# POWER_BANK_PART.net
KiCad netlist of a schematic drawn in Altium Designer
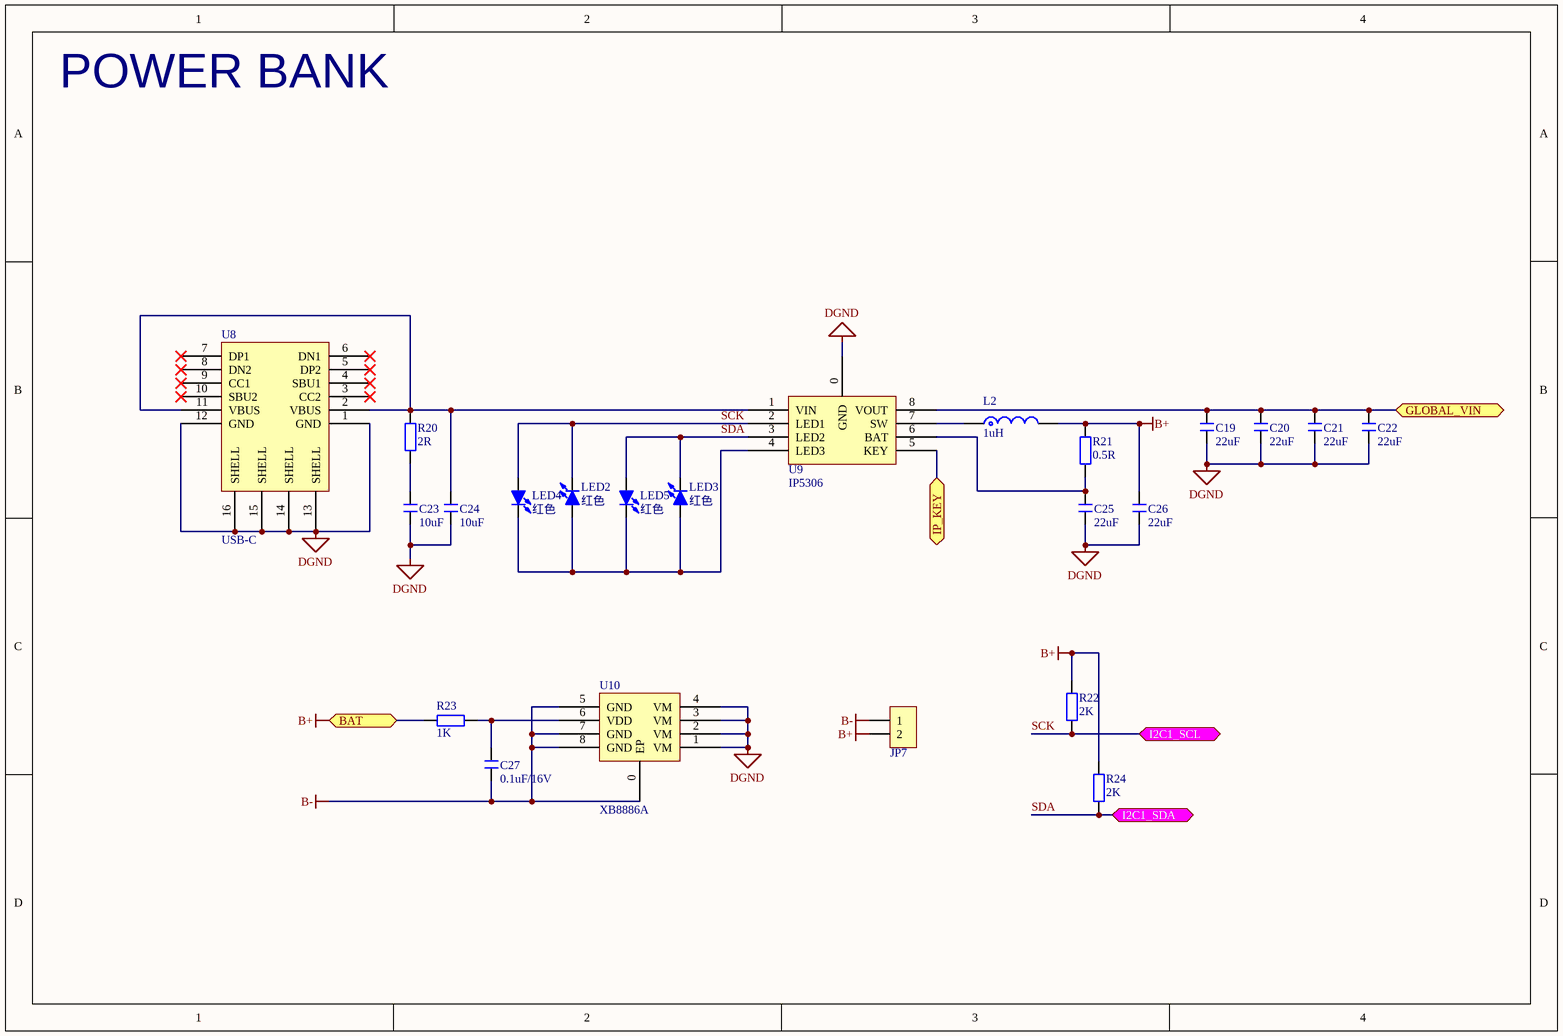
[diagram p0: POWER_BANK_PART.SchDoc]

(export (version "E")
  (design (tool "Eeschema 10.0.6"))
  (components
    (comp (ref "C19")
      (value "22uF")
      (footprint "C 0603_L")
      (description "无极性贴片电容")
      (fields (field (name "版权归属") "源创客"))
      (libsource (lib "3.1   - 电阻-电容-电感") (part "C"))
    )
    (comp (ref "C20")
      (value "22uF")
      (footprint "C 0603_L")
      (description "无极性贴片电容")
      (fields (field (name "版权归属") "源创客"))
      (libsource (lib "3.1   - 电阻-电容-电感") (part "C"))
    )
    (comp (ref "C21")
      (value "22uF")
      (footprint "C 0603_L")
      (description "无极性贴片电容")
      (fields (field (name "版权归属") "源创客"))
      (libsource (lib "3.1   - 电阻-电容-电感") (part "C"))
    )
    (comp (ref "C22")
      (value "22uF")
      (footprint "C 0603_L")
      (description "无极性贴片电容")
      (fields (field (name "版权归属") "源创客"))
      (libsource (lib "3.1   - 电阻-电容-电感") (part "C"))
    )
    (comp (ref "C23")
      (value "10uF")
      (footprint "C 0603_L")
      (description "无极性贴片电容")
      (fields (field (name "版权归属") "源创客"))
      (libsource (lib "3.1   - 电阻-电容-电感") (part "C"))
    )
    (comp (ref "C24")
      (value "10uF")
      (footprint "C 0603_L")
      (description "无极性贴片电容")
      (fields (field (name "版权归属") "源创客"))
      (libsource (lib "3.1   - 电阻-电容-电感") (part "C"))
    )
    (comp (ref "C25")
      (value "22uF")
      (footprint "C 0603_L")
      (description "无极性贴片电容")
      (fields (field (name "版权归属") "源创客"))
      (libsource (lib "3.1   - 电阻-电容-电感") (part "C"))
    )
    (comp (ref "C26")
      (value "22uF")
      (footprint "C 0603_L")
      (description "无极性贴片电容")
      (fields (field (name "版权归属") "源创客"))
      (libsource (lib "3.1   - 电阻-电容-电感") (part "C"))
    )
    (comp (ref "C27")
      (value "0.1uF/16V")
      (footprint "C 0603_L")
      (description "无极性贴片电容")
      (fields (field (name "版权归属") "源创客"))
      (libsource (lib "3.1   - 电阻-电容-电感") (part "C"))
    )
    (comp (ref "JP7")
      (value "HDR-1X2")
      (footprint "KF301-5.0-2P")
      (description "2P接插件")
      (fields (field (name "版权归属") "源创客"))
      (libsource (lib "4.9   - 接插件-脚距5.0") (part "Header 2"))
    )
    (comp (ref "L2")
      (value "1uH")
      (footprint "CD43")
      (description "贴片功率电感")
      (fields (field (name "版权归属") "源创客"))
      (libsource (lib "3.1   - 电阻-电容-电感") (part "L-CD"))
    )
    (comp (ref "LED2")
      (value "红色")
      (footprint "LED 0603W")
      (description "贴片LED")
      (fields (field (name "版权归属") "源创客"))
      (libsource (lib "9.1   - LED") (part "LED-SMD"))
    )
    (comp (ref "LED3")
      (value "红色")
      (footprint "LED 0603W")
      (description "贴片LED")
      (fields (field (name "版权归属") "源创客"))
      (libsource (lib "9.1   - LED") (part "LED-SMD"))
    )
    (comp (ref "LED4")
      (value "红色")
      (footprint "LED 0603W")
      (description "贴片LED")
      (fields (field (name "版权归属") "源创客"))
      (libsource (lib "9.1   - LED") (part "LED-SMD"))
    )
    (comp (ref "LED5")
      (value "红色")
      (footprint "LED 0603W")
      (description "贴片LED")
      (fields (field (name "版权归属") "源创客"))
      (libsource (lib "9.1   - LED") (part "LED-SMD"))
    )
    (comp (ref "R20")
      (value "2R")
      (footprint "R 0603_L")
      (description "贴片电阻")
      (fields (field (name "版权归属") "源创客"))
      (libsource (lib "3.1   - 电阻-电容-电感") (part "R"))
    )
    (comp (ref "R21")
      (value "0.5R")
      (footprint "R 0603_L")
      (description "贴片电阻")
      (fields (field (name "版权归属") "源创客"))
      (libsource (lib "3.1   - 电阻-电容-电感") (part "R"))
    )
    (comp (ref "R22")
      (value "2K")
      (footprint "R 0603_L")
      (description "贴片电阻")
      (fields (field (name "版权归属") "源创客"))
      (libsource (lib "3.1   - 电阻-电容-电感") (part "R"))
    )
    (comp (ref "R23")
      (value "1K")
      (footprint "R 0603_L")
      (description "贴片电阻")
      (fields (field (name "版权归属") "源创客"))
      (libsource (lib "3.1   - 电阻-电容-电感") (part "R"))
    )
    (comp (ref "R24")
      (value "2K")
      (footprint "R 0603_L")
      (description "贴片电阻")
      (fields (field (name "版权归属") "源创客"))
      (libsource (lib "3.1   - 电阻-电容-电感") (part "R"))
    )
    (comp (ref "U8")
      (value "USB-C")
      (footprint "USB-C-16")
      (description "USB-C型母接口")
      (fields (field (name "版权归属") "源创客"))
      (libsource (lib "示波器") (part "USB-C-16P"))
    )
    (comp (ref "U9")
      (value "IP5306")
      (footprint "SOP-8-G")
      (description "电源芯片")
      (libsource (lib "示波器") (part "IP5306"))
    )
    (comp (ref "U10")
      (value "XB8886A")
      (footprint "SOP-8-G")
      (description "锂电池保护芯片")
      (libsource (lib "示波器") (part "XB8886A"))
    )
  )
  (nets
    (net (code "1") (name "/GLOBAL_VIN") (class "Default")
      (node (ref "C19") (pin "1") (pinfunction "1_1") (pintype "passive"))
      (node (ref "C20") (pin "1") (pinfunction "1_1") (pintype "passive"))
      (node (ref "C21") (pin "1") (pinfunction "1_1") (pintype "passive"))
      (node (ref "C22") (pin "1") (pinfunction "1_1") (pintype "passive"))
      (node (ref "U9") (pin "8") (pinfunction "VOUT_8") (pintype "passive"))
    )
    (net (code "2") (name "/IP_KEY") (class "Default")
      (node (ref "U9") (pin "5") (pinfunction "KEY_5") (pintype "passive"))
    )
    (net (code "3") (name "/SCK") (class "Default")
      (node (ref "LED2") (pin "2") (pinfunction "K_2") (pintype "passive"))
      (node (ref "LED4") (pin "1") (pinfunction "A_1") (pintype "passive"))
      (node (ref "R22") (pin "1") (pinfunction "1_1") (pintype "passive"))
      (node (ref "U9") (pin "2") (pinfunction "LED1_2") (pintype "passive"))
    )
    (net (code "4") (name "/SDA") (class "Default")
      (node (ref "LED3") (pin "2") (pinfunction "K_2") (pintype "passive"))
      (node (ref "LED5") (pin "1") (pinfunction "A_1") (pintype "passive"))
      (node (ref "R24") (pin "1") (pinfunction "1_1") (pintype "passive"))
      (node (ref "U9") (pin "3") (pinfunction "LED2_3") (pintype "passive"))
    )
    (net (code "5") (name "B+") (class "Default")
      (node (ref "C26") (pin "1") (pinfunction "1_1") (pintype "passive"))
      (node (ref "JP7") (pin "2") (pinfunction "2_2") (pintype "passive"))
      (node (ref "L2") (pin "2") (pinfunction "2_2") (pintype "passive"))
      (node (ref "R21") (pin "2") (pinfunction "2_2") (pintype "passive"))
      (node (ref "R22") (pin "2") (pinfunction "2_2") (pintype "passive"))
      (node (ref "R23") (pin "1") (pinfunction "1_1") (pintype "passive"))
      (node (ref "R24") (pin "2") (pinfunction "2_2") (pintype "passive"))
    )
    (net (code "6") (name "B-") (class "Default")
      (node (ref "C27") (pin "2") (pinfunction "2_2") (pintype "passive"))
      (node (ref "JP7") (pin "1") (pinfunction "1_1") (pintype "passive"))
      (node (ref "U10") (pin "0") (pinfunction "EP_0") (pintype "passive"))
      (node (ref "U10") (pin "5") (pinfunction "GND_5") (pintype "passive"))
      (node (ref "U10") (pin "7") (pinfunction "GND_7") (pintype "passive"))
      (node (ref "U10") (pin "8") (pinfunction "GND_8") (pintype "passive"))
    )
    (net (code "7") (name "DGND") (class "Default")
      (node (ref "C19") (pin "2") (pinfunction "2_2") (pintype "passive"))
      (node (ref "C20") (pin "2") (pinfunction "2_2") (pintype "passive"))
      (node (ref "C21") (pin "2") (pinfunction "2_2") (pintype "passive"))
      (node (ref "C22") (pin "2") (pinfunction "2_2") (pintype "passive"))
      (node (ref "C23") (pin "2") (pinfunction "2_2") (pintype "passive"))
      (node (ref "C24") (pin "2") (pinfunction "2_2") (pintype "passive"))
      (node (ref "C25") (pin "2") (pinfunction "2_2") (pintype "passive"))
      (node (ref "C26") (pin "2") (pinfunction "2_2") (pintype "passive"))
      (node (ref "U10") (pin "1") (pinfunction "VM_1") (pintype "passive"))
      (node (ref "U10") (pin "2") (pinfunction "VM_2") (pintype "passive"))
      (node (ref "U10") (pin "3") (pinfunction "VM_3") (pintype "passive"))
      (node (ref "U10") (pin "4") (pinfunction "VM_4") (pintype "passive"))
      (node (ref "U8") (pin "1") (pinfunction "GND_1") (pintype "passive"))
      (node (ref "U8") (pin "12") (pinfunction "GND_12") (pintype "passive"))
      (node (ref "U8") (pin "13") (pinfunction "SHELL_13") (pintype "passive"))
      (node (ref "U8") (pin "14") (pinfunction "SHELL_14") (pintype "passive"))
      (node (ref "U8") (pin "15") (pinfunction "SHELL_15") (pintype "passive"))
      (node (ref "U8") (pin "16") (pinfunction "SHELL_16") (pintype "passive"))
      (node (ref "U9") (pin "0") (pinfunction "GND_0") (pintype "passive"))
    )
    (net (code "8") (name "Net-(C23-Pad1)") (class "Default")
      (node (ref "C23") (pin "1") (pinfunction "1_1") (pintype "passive"))
      (node (ref "R20") (pin "1") (pinfunction "1_1") (pintype "passive"))
    )
    (net (code "9") (name "Net-(LED2-A)") (class "Default")
      (node (ref "LED2") (pin "1") (pinfunction "A_1") (pintype "passive"))
      (node (ref "LED3") (pin "1") (pinfunction "A_1") (pintype "passive"))
      (node (ref "LED4") (pin "2") (pinfunction "K_2") (pintype "passive"))
      (node (ref "LED5") (pin "2") (pinfunction "K_2") (pintype "passive"))
      (node (ref "U9") (pin "4") (pinfunction "LED3_4") (pintype "passive"))
    )
    (net (code "10") (name "Net-(U9-BAT)") (class "Default")
      (node (ref "C25") (pin "1") (pinfunction "1_1") (pintype "passive"))
      (node (ref "R21") (pin "1") (pinfunction "1_1") (pintype "passive"))
      (node (ref "U9") (pin "6") (pinfunction "BAT_6") (pintype "passive"))
    )
    (net (code "11") (name "Net-(U9-SW)") (class "Default")
      (node (ref "L2") (pin "1") (pinfunction "1_1") (pintype "passive"))
      (node (ref "U9") (pin "7") (pinfunction "SW_7") (pintype "passive"))
    )
    (net (code "12") (name "Net-(U9-VIN)") (class "Default")
      (node (ref "C24") (pin "1") (pinfunction "1_1") (pintype "passive"))
      (node (ref "R20") (pin "2") (pinfunction "2_2") (pintype "passive"))
      (node (ref "U8") (pin "11") (pinfunction "VBUS_11") (pintype "passive"))
      (node (ref "U8") (pin "2") (pinfunction "VBUS_2") (pintype "passive"))
      (node (ref "U9") (pin "1") (pinfunction "VIN_1") (pintype "passive"))
    )
    (net (code "13") (name "Net-(U10-VDD)") (class "Default")
      (node (ref "C27") (pin "1") (pinfunction "1_1") (pintype "passive"))
      (node (ref "R23") (pin "2") (pinfunction "2_2") (pintype "passive"))
      (node (ref "U10") (pin "6") (pinfunction "VDD_6") (pintype "passive"))
    )
    (net (code "14") (name "unconnected-(U8-CC1-Pad9)") (class "Default")
      (node (ref "U8") (pin "9") (pinfunction "CC1_9") (pintype "passive+no_connect"))
    )
    (net (code "15") (name "unconnected-(U8-CC2-Pad3)") (class "Default")
      (node (ref "U8") (pin "3") (pinfunction "CC2_3") (pintype "passive+no_connect"))
    )
    (net (code "16") (name "unconnected-(U8-DN1-Pad6)") (class "Default")
      (node (ref "U8") (pin "6") (pinfunction "DN1_6") (pintype "passive+no_connect"))
    )
    (net (code "17") (name "unconnected-(U8-DN2-Pad8)") (class "Default")
      (node (ref "U8") (pin "8") (pinfunction "DN2_8") (pintype "passive+no_connect"))
    )
    (net (code "18") (name "unconnected-(U8-DP1-Pad7)") (class "Default")
      (node (ref "U8") (pin "7") (pinfunction "DP1_7") (pintype "passive+no_connect"))
    )
    (net (code "19") (name "unconnected-(U8-DP2-Pad5)") (class "Default")
      (node (ref "U8") (pin "5") (pinfunction "DP2_5") (pintype "passive+no_connect"))
    )
    (net (code "20") (name "unconnected-(U8-SBU1-Pad4)") (class "Default")
      (node (ref "U8") (pin "4") (pinfunction "SBU1_4") (pintype "passive+no_connect"))
    )
    (net (code "21") (name "unconnected-(U8-SBU2-Pad10)") (class "Default")
      (node (ref "U8") (pin "10") (pinfunction "SBU2_10") (pintype "passive+no_connect"))
    )
  )
)
